# Schematic_Interface_Lio_with_IC.net
KiCad netlist of a schematic drawn in Altium Designer
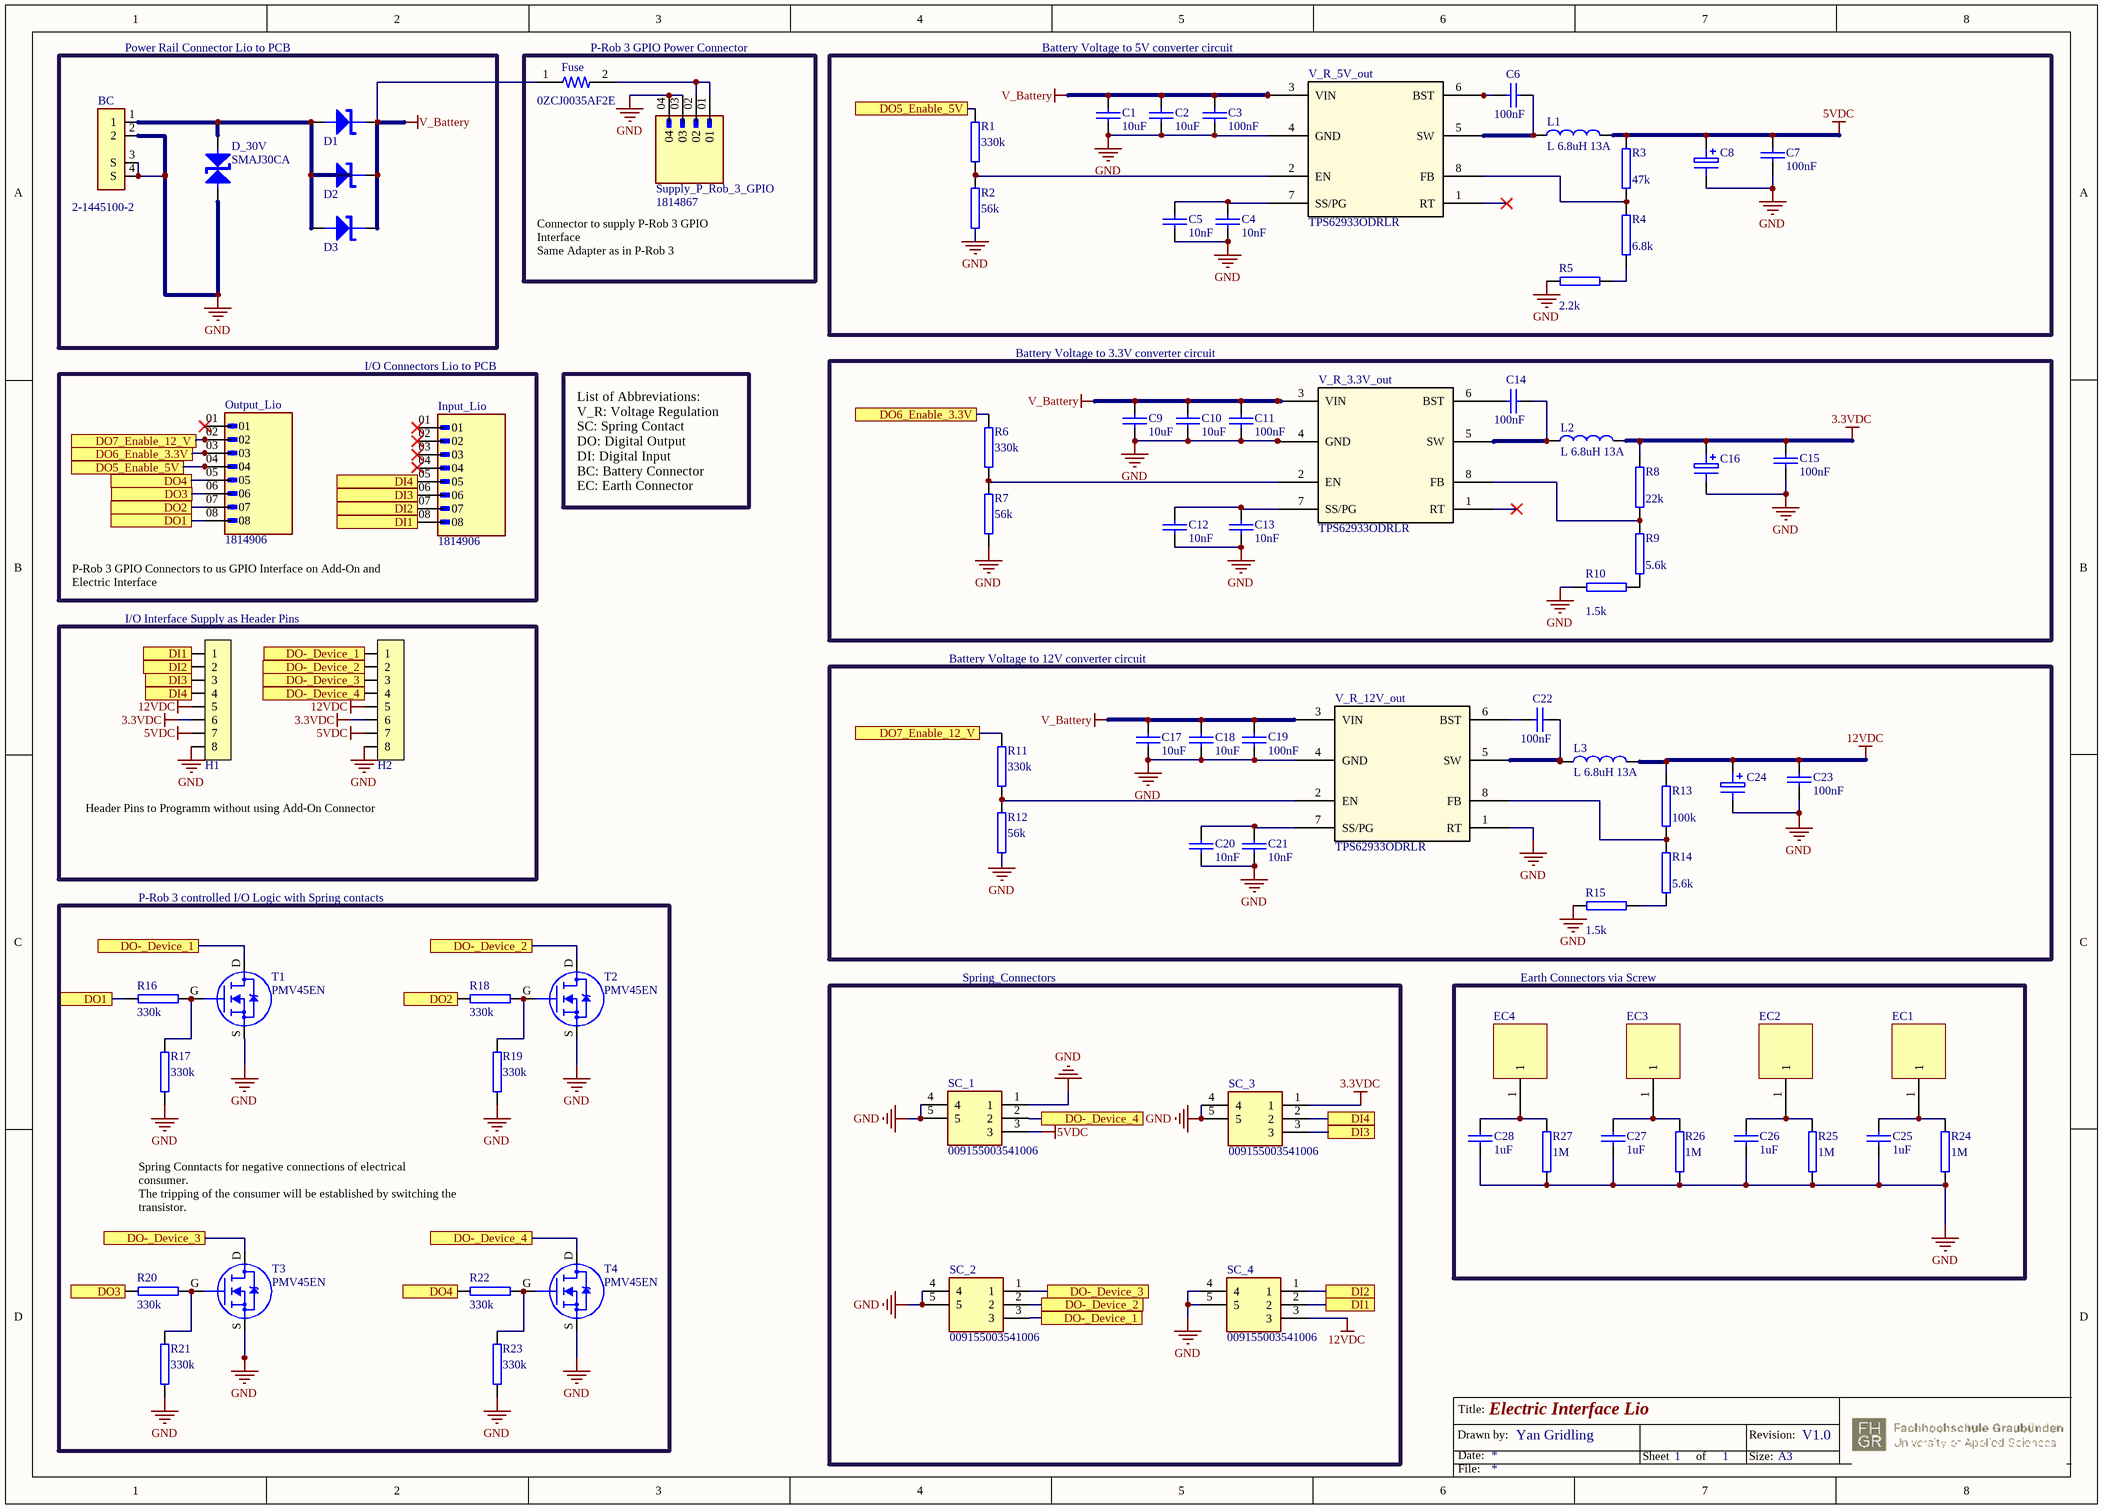
[diagram p0: Schematic_Interface_Lio_with_IC.SchDoc]

(export (version "E")
  (design (tool "Eeschema 10.0.6"))
  (components
    (comp (ref "BC")
      (value "2-1445100-2")
      (footprint "2-1445100-2")
      (description "Micro MATE-N-LOK 2 Position Surface Mount Single Row Straight 3 mm Pin Header")
      (fields (field (name "MF") "TE Connectivity") (field (name "MP") "2-1445053-2"))
      (libsource (lib "Electric_Interface_Lib") (part "2-1445100-2"))
    )
    (comp (ref "C1")
      (value "10uF")
      (footprint "C_1210_A")
      (fields
        (field (name "TOLERANCE") "10%")
        (field (name "VOLTAGE") "50V")
        (field (name "Comment") "C 10uF 1210")
      )
      (libsource (lib "FHGR_Altium_database") (part "Capacitor"))
    )
    (comp (ref "C2")
      (value "10uF")
      (footprint "C_1210_A")
      (fields
        (field (name "TOLERANCE") "10%")
        (field (name "VOLTAGE") "50V")
        (field (name "Comment") "C 10uF 1210")
      )
      (libsource (lib "FHGR_Altium_database") (part "Capacitor"))
    )
    (comp (ref "C3")
      (value "100nF")
      (footprint "0603")
      (fields
        (field (name "TOLERANCE") "-20%/+80%")
        (field (name "VOLTAGE") "50V")
        (field (name "Comment") "C 100nF 0603")
      )
      (libsource (lib "FHGR_Altium_database") (part "Capacitor"))
    )
    (comp (ref "C4")
      (value "10nF")
      (footprint "0603")
      (fields
        (field (name "TOLERANCE") "10%")
        (field (name "VOLTAGE") "50V")
        (field (name "Comment") "C 10nF 0603")
      )
      (libsource (lib "FHGR_Altium_database") (part "Capacitor"))
    )
    (comp (ref "C5")
      (value "10nF")
      (footprint "0603")
      (fields
        (field (name "TOLERANCE") "10%")
        (field (name "VOLTAGE") "50V")
        (field (name "Comment") "C 10nF 0603")
      )
      (libsource (lib "FHGR_Altium_database") (part "Capacitor"))
    )
    (comp (ref "C6")
      (value "100nF")
      (footprint "0603")
      (fields
        (field (name "TOLERANCE") "-20%/+80%")
        (field (name "VOLTAGE") "50V")
        (field (name "Comment") "C 100nF 0603")
      )
      (libsource (lib "FHGR_Altium_database") (part "Capacitor"))
    )
    (comp (ref "C7")
      (value "100nF")
      (footprint "0603")
      (fields
        (field (name "TOLERANCE") "-20%/+80%")
        (field (name "VOLTAGE") "50V")
        (field (name "Comment") "C 100nF 0603")
      )
      (libsource (lib "FHGR_Altium_database") (part "Capacitor"))
    )
    (comp (ref "C8")
      (value "C 47uF ALUM")
      (footprint "HA1C470WR")
      (fields (field (name "TOLERANCE") "20%") (field (name "VOLTAGE") "16V"))
      (libsource (lib "FHGR_Altium_database") (part "Capacitor_Pol"))
    )
    (comp (ref "C9")
      (value "10uF")
      (footprint "C_1210_A")
      (fields
        (field (name "TOLERANCE") "10%")
        (field (name "VOLTAGE") "50V")
        (field (name "Comment") "C 10uF 1210")
      )
      (libsource (lib "FHGR_Altium_database") (part "Capacitor"))
    )
    (comp (ref "C10")
      (value "10uF")
      (footprint "C_1210_A")
      (fields
        (field (name "TOLERANCE") "10%")
        (field (name "VOLTAGE") "50V")
        (field (name "Comment") "C 10uF 1210")
      )
      (libsource (lib "FHGR_Altium_database") (part "Capacitor"))
    )
    (comp (ref "C11")
      (value "100nF")
      (footprint "0603")
      (fields
        (field (name "TOLERANCE") "-20%/+80%")
        (field (name "VOLTAGE") "50V")
        (field (name "Comment") "C 100nF 0603")
      )
      (libsource (lib "FHGR_Altium_database") (part "Capacitor"))
    )
    (comp (ref "C12")
      (value "10nF")
      (footprint "0603")
      (fields
        (field (name "TOLERANCE") "10%")
        (field (name "VOLTAGE") "50V")
        (field (name "Comment") "C 10nF 0603")
      )
      (libsource (lib "FHGR_Altium_database") (part "Capacitor"))
    )
    (comp (ref "C13")
      (value "10nF")
      (footprint "0603")
      (fields
        (field (name "TOLERANCE") "10%")
        (field (name "VOLTAGE") "50V")
        (field (name "Comment") "C 10nF 0603")
      )
      (libsource (lib "FHGR_Altium_database") (part "Capacitor"))
    )
    (comp (ref "C14")
      (value "100nF")
      (footprint "0603")
      (fields
        (field (name "TOLERANCE") "-20%/+80%")
        (field (name "VOLTAGE") "50V")
        (field (name "Comment") "C 100nF 0603")
      )
      (libsource (lib "FHGR_Altium_database") (part "Capacitor"))
    )
    (comp (ref "C15")
      (value "100nF")
      (footprint "0603")
      (fields
        (field (name "TOLERANCE") "-20%/+80%")
        (field (name "VOLTAGE") "50V")
        (field (name "Comment") "C 100nF 0603")
      )
      (libsource (lib "FHGR_Altium_database") (part "Capacitor"))
    )
    (comp (ref "C16")
      (value "C 47uF ALUM")
      (footprint "HA1C470WR")
      (fields (field (name "TOLERANCE") "20%") (field (name "VOLTAGE") "16V"))
      (libsource (lib "FHGR_Altium_database") (part "Capacitor_Pol"))
    )
    (comp (ref "C17")
      (value "10uF")
      (footprint "C_1210_A")
      (fields
        (field (name "TOLERANCE") "10%")
        (field (name "VOLTAGE") "50V")
        (field (name "Comment") "C 10uF 1210")
      )
      (libsource (lib "FHGR_Altium_database") (part "Capacitor"))
    )
    (comp (ref "C18")
      (value "10uF")
      (footprint "C_1210_A")
      (fields
        (field (name "TOLERANCE") "10%")
        (field (name "VOLTAGE") "50V")
        (field (name "Comment") "C 10uF 1210")
      )
      (libsource (lib "FHGR_Altium_database") (part "Capacitor"))
    )
    (comp (ref "C19")
      (value "100nF")
      (footprint "0603")
      (fields
        (field (name "TOLERANCE") "-20%/+80%")
        (field (name "VOLTAGE") "50V")
        (field (name "Comment") "C 100nF 0603")
      )
      (libsource (lib "FHGR_Altium_database") (part "Capacitor"))
    )
    (comp (ref "C20")
      (value "10nF")
      (footprint "0603")
      (fields
        (field (name "TOLERANCE") "10%")
        (field (name "VOLTAGE") "50V")
        (field (name "Comment") "C 10nF 0603")
      )
      (libsource (lib "FHGR_Altium_database") (part "Capacitor"))
    )
    (comp (ref "C21")
      (value "10nF")
      (footprint "0603")
      (fields
        (field (name "TOLERANCE") "10%")
        (field (name "VOLTAGE") "50V")
        (field (name "Comment") "C 10nF 0603")
      )
      (libsource (lib "FHGR_Altium_database") (part "Capacitor"))
    )
    (comp (ref "C22")
      (value "100nF")
      (footprint "0603")
      (fields
        (field (name "TOLERANCE") "-20%/+80%")
        (field (name "VOLTAGE") "50V")
        (field (name "Comment") "C 100nF 0603")
      )
      (libsource (lib "FHGR_Altium_database") (part "Capacitor"))
    )
    (comp (ref "C23")
      (value "100nF")
      (footprint "0603")
      (fields
        (field (name "TOLERANCE") "-20%/+80%")
        (field (name "VOLTAGE") "50V")
        (field (name "Comment") "C 100nF 0603")
      )
      (libsource (lib "FHGR_Altium_database") (part "Capacitor"))
    )
    (comp (ref "C24")
      (value "C 47uF ALUM")
      (footprint "HA1C470WR")
      (fields (field (name "TOLERANCE") "20%") (field (name "VOLTAGE") "16V"))
      (libsource (lib "FHGR_Altium_database") (part "Capacitor_Pol"))
    )
    (comp (ref "C25")
      (value "1uF")
      (footprint "0603")
      (fields
        (field (name "TOLERANCE") "10%")
        (field (name "VOLTAGE") "25V")
        (field (name "Comment") "C 1uF 0603")
      )
      (libsource (lib "FHGR_Altium_database") (part "Capacitor"))
    )
    (comp (ref "C26")
      (value "1uF")
      (footprint "0603")
      (fields
        (field (name "TOLERANCE") "10%")
        (field (name "VOLTAGE") "25V")
        (field (name "Comment") "C 1uF 0603")
      )
      (libsource (lib "FHGR_Altium_database") (part "Capacitor"))
    )
    (comp (ref "C27")
      (value "1uF")
      (footprint "0603")
      (fields
        (field (name "TOLERANCE") "10%")
        (field (name "VOLTAGE") "25V")
        (field (name "Comment") "C 1uF 0603")
      )
      (libsource (lib "FHGR_Altium_database") (part "Capacitor"))
    )
    (comp (ref "C28")
      (value "1uF")
      (footprint "0603")
      (fields
        (field (name "TOLERANCE") "10%")
        (field (name "VOLTAGE") "25V")
        (field (name "Comment") "C 1uF 0603")
      )
      (libsource (lib "FHGR_Altium_database") (part "Capacitor"))
    )
    (comp (ref "D1")
      (value "Schottky 60V/2A")
      (footprint "SOD-123FL")
      (fields (field (name "VOLTAGE") "60V"))
      (libsource (lib "FHGR_Altium_database") (part "SchottkyDiode"))
    )
    (comp (ref "D2")
      (value "Schottky 60V/2A")
      (footprint "SOD-123FL")
      (fields (field (name "VOLTAGE") "60V"))
      (libsource (lib "FHGR_Altium_database") (part "SchottkyDiode"))
    )
    (comp (ref "D3")
      (value "Schottky 60V/2A")
      (footprint "SOD-123FL")
      (fields (field (name "VOLTAGE") "60V"))
      (libsource (lib "FHGR_Altium_database") (part "SchottkyDiode"))
    )
    (comp (ref "D_30V")
      (value "SMAJ30CA")
      (footprint "SMA")
      (description "Cera Diode 30 Volt Overvoltage protection.")
      (fields (field (name "VOLTAGE") "30V"))
      (libsource (lib "FHGR_Altium_database") (part "CeraDiode"))
    )
    (comp (ref "EC1")
      (value "Screw_Earth_Connection")
      (footprint "Screw_Earth_Connector_Pad")
      (libsource (lib "Electric_Interface_Lib") (part "Screw_Earth_Connection"))
    )
    (comp (ref "EC2")
      (value "Screw_Earth_Connection")
      (footprint "Screw_Earth_Connector_Pad")
      (libsource (lib "Electric_Interface_Lib") (part "Screw_Earth_Connection"))
    )
    (comp (ref "EC3")
      (value "Screw_Earth_Connection")
      (footprint "Screw_Earth_Connector_Pad")
      (libsource (lib "Electric_Interface_Lib") (part "Screw_Earth_Connection"))
    )
    (comp (ref "EC4")
      (value "Screw_Earth_Connection")
      (footprint "Screw_Earth_Connector_Pad")
      (libsource (lib "Electric_Interface_Lib") (part "Screw_Earth_Connection"))
    )
    (comp (ref "Fuse")
      (value "0ZCJ0035AF2E")
      (footprint "RESC3216X125N")
      (description "1206 SMT PPTC ¦ 0.35 Ih ¦ 30V")
      (fields (field (name "MF") "Bel Fuse"))
      (libsource (lib "Electric_Interface_Lib") (part "0ZCJ0035AF2E"))
    )
    (comp (ref "H1")
      (value "8Pin_Male")
      (footprint "Header1x8_254")
      (libsource (lib "FHGR_Altium_database") (part "Connector8Pin"))
    )
    (comp (ref "H2")
      (value "8Pin_Male")
      (footprint "Header1x8_254")
      (libsource (lib "FHGR_Altium_database") (part "Connector8Pin"))
    )
    (comp (ref "Input_Lio")
      (value "1814906")
      (footprint "PHOENIX_1814906")
      (fields (field (name "MF") "{'manufacturer': u'Phoenix Contact'}"))
      (libsource (lib "Electric_Interface_Lib") (part "1814906"))
    )
    (comp (ref "L1")
      (value "L 6.8uH 13A")
      (footprint "SRP1040VA-6R8M")
      (libsource (lib "Electric_Interface_Lib") (part "SRP1040VA-6R8M"))
    )
    (comp (ref "L2")
      (value "L 6.8uH 13A")
      (footprint "SRP1040VA-6R8M")
      (libsource (lib "Electric_Interface_Lib") (part "SRP1040VA-6R8M"))
    )
    (comp (ref "L3")
      (value "L 6.8uH 13A")
      (footprint "SRP1040VA-6R8M")
      (libsource (lib "Electric_Interface_Lib") (part "SRP1040VA-6R8M"))
    )
    (comp (ref "Output_Lio")
      (value "1814906")
      (footprint "PHOENIX_1814906")
      (fields (field (name "MF") "{'manufacturer': u'Phoenix Contact'}"))
      (libsource (lib "Electric_Interface_Lib") (part "1814906"))
    )
    (comp (ref "R1")
      (value "330k")
      (footprint "0805")
      (fields (field (name "TOLERANCE") "1%") (field (name "Comment") "R 330K 0805"))
      (libsource (lib "FHGR_Altium_database") (part "Resistor"))
    )
    (comp (ref "R2")
      (value "56k")
      (footprint "0805")
      (fields (field (name "TOLERANCE") "1%") (field (name "Comment") "R 56K 0805"))
      (libsource (lib "FHGR_Altium_database") (part "Resistor"))
    )
    (comp (ref "R3")
      (value "47k")
      (footprint "0805")
      (fields (field (name "TOLERANCE") "1%") (field (name "Comment") "R 47K 0805"))
      (libsource (lib "FHGR_Altium_database") (part "Resistor"))
    )
    (comp (ref "R4")
      (value "6.8k")
      (footprint "0805")
      (fields (field (name "TOLERANCE") "1%") (field (name "Comment") "R 6K8 0805"))
      (libsource (lib "FHGR_Altium_database") (part "Resistor"))
    )
    (comp (ref "R5")
      (value "2.2k")
      (footprint "0805")
      (fields (field (name "TOLERANCE") "1%") (field (name "Comment") "R 2K2 0805"))
      (libsource (lib "FHGR_Altium_database") (part "Resistor"))
    )
    (comp (ref "R6")
      (value "330k")
      (footprint "0805")
      (fields (field (name "TOLERANCE") "1%") (field (name "Comment") "R 330K 0805"))
      (libsource (lib "FHGR_Altium_database") (part "Resistor"))
    )
    (comp (ref "R7")
      (value "56k")
      (footprint "0805")
      (fields (field (name "TOLERANCE") "1%") (field (name "Comment") "R 56K 0805"))
      (libsource (lib "FHGR_Altium_database") (part "Resistor"))
    )
    (comp (ref "R8")
      (value "22k")
      (footprint "0805")
      (fields (field (name "TOLERANCE") "1%") (field (name "Comment") "R 22K 0805"))
      (libsource (lib "FHGR_Altium_database") (part "Resistor"))
    )
    (comp (ref "R9")
      (value "5.6k")
      (footprint "0805")
      (fields (field (name "TOLERANCE") "1%") (field (name "Comment") "R 5K6 0805"))
      (libsource (lib "FHGR_Altium_database") (part "Resistor"))
    )
    (comp (ref "R10")
      (value "1.5k")
      (footprint "0805")
      (fields (field (name "TOLERANCE") "1%") (field (name "Comment") "R 1K5 0805"))
      (libsource (lib "FHGR_Altium_database") (part "Resistor"))
    )
    (comp (ref "R11")
      (value "330k")
      (footprint "0805")
      (fields (field (name "TOLERANCE") "1%") (field (name "Comment") "R 330K 0805"))
      (libsource (lib "FHGR_Altium_database") (part "Resistor"))
    )
    (comp (ref "R12")
      (value "56k")
      (footprint "0805")
      (fields (field (name "TOLERANCE") "1%") (field (name "Comment") "R 56K 0805"))
      (libsource (lib "FHGR_Altium_database") (part "Resistor"))
    )
    (comp (ref "R13")
      (value "100k")
      (footprint "0805")
      (fields (field (name "TOLERANCE") "1%") (field (name "Comment") "R 100K 0805"))
      (libsource (lib "FHGR_Altium_database") (part "Resistor"))
    )
    (comp (ref "R14")
      (value "5.6k")
      (footprint "0805")
      (fields (field (name "TOLERANCE") "1%") (field (name "Comment") "R 5K6 0805"))
      (libsource (lib "FHGR_Altium_database") (part "Resistor"))
    )
    (comp (ref "R15")
      (value "1.5k")
      (footprint "0805")
      (fields (field (name "TOLERANCE") "1%") (field (name "Comment") "R 1K5 0805"))
      (libsource (lib "FHGR_Altium_database") (part "Resistor"))
    )
    (comp (ref "R16")
      (value "330k")
      (footprint "0805")
      (fields (field (name "TOLERANCE") "1%") (field (name "Comment") "R 330K 0805"))
      (libsource (lib "FHGR_Altium_database") (part "Resistor"))
    )
    (comp (ref "R17")
      (value "330k")
      (footprint "0805")
      (fields (field (name "TOLERANCE") "1%") (field (name "Comment") "R 330K 0805"))
      (libsource (lib "FHGR_Altium_database") (part "Resistor"))
    )
    (comp (ref "R18")
      (value "330k")
      (footprint "0805")
      (fields (field (name "TOLERANCE") "1%") (field (name "Comment") "R 330K 0805"))
      (libsource (lib "FHGR_Altium_database") (part "Resistor"))
    )
    (comp (ref "R19")
      (value "330k")
      (footprint "0805")
      (fields (field (name "TOLERANCE") "1%") (field (name "Comment") "R 330K 0805"))
      (libsource (lib "FHGR_Altium_database") (part "Resistor"))
    )
    (comp (ref "R20")
      (value "330k")
      (footprint "0805")
      (fields (field (name "TOLERANCE") "1%") (field (name "Comment") "R 330K 0805"))
      (libsource (lib "FHGR_Altium_database") (part "Resistor"))
    )
    (comp (ref "R21")
      (value "330k")
      (footprint "0805")
      (fields (field (name "TOLERANCE") "1%") (field (name "Comment") "R 330K 0805"))
      (libsource (lib "FHGR_Altium_database") (part "Resistor"))
    )
    (comp (ref "R22")
      (value "330k")
      (footprint "0805")
      (fields (field (name "TOLERANCE") "1%") (field (name "Comment") "R 330K 0805"))
      (libsource (lib "FHGR_Altium_database") (part "Resistor"))
    )
    (comp (ref "R23")
      (value "330k")
      (footprint "0805")
      (fields (field (name "TOLERANCE") "1%") (field (name "Comment") "R 330K 0805"))
      (libsource (lib "FHGR_Altium_database") (part "Resistor"))
    )
    (comp (ref "R24")
      (value "1M")
      (footprint "0805")
      (fields (field (name "TOLERANCE") "1%") (field (name "Comment") "R 1M 0805"))
      (libsource (lib "FHGR_Altium_database") (part "Resistor"))
    )
    (comp (ref "R25")
      (value "1M")
      (footprint "0805")
      (fields (field (name "TOLERANCE") "1%") (field (name "Comment") "R 1M 0805"))
      (libsource (lib "FHGR_Altium_database") (part "Resistor"))
    )
    (comp (ref "R26")
      (value "1M")
      (footprint "0805")
      (fields (field (name "TOLERANCE") "1%") (field (name "Comment") "R 1M 0805"))
      (libsource (lib "FHGR_Altium_database") (part "Resistor"))
    )
    (comp (ref "R27")
      (value "1M")
      (footprint "0805")
      (fields (field (name "TOLERANCE") "1%") (field (name "Comment") "R 1M 0805"))
      (libsource (lib "FHGR_Altium_database") (part "Resistor"))
    )
    (comp (ref "SC_1")
      (value "009155003541006")
      (footprint "009155003541006")
      (description "Connector")
      (fields (field (name "MOUSER PART NUMBER") "581-009155003541006"))
      (libsource (lib "Electric_Interface_Lib") (part "009155003541006"))
    )
    (comp (ref "SC_2")
      (value "009155003541006")
      (footprint "009155003541006")
      (description "Connector")
      (fields (field (name "MOUSER PART NUMBER") "581-009155003541006"))
      (libsource (lib "Electric_Interface_Lib") (part "009155003541006"))
    )
    (comp (ref "SC_3")
      (value "009155003541006")
      (footprint "009155003541006")
      (description "Connector")
      (fields (field (name "MOUSER PART NUMBER") "581-009155003541006"))
      (libsource (lib "Electric_Interface_Lib") (part "009155003541006"))
    )
    (comp (ref "SC_4")
      (value "009155003541006")
      (footprint "009155003541006")
      (description "Connector")
      (fields (field (name "MOUSER PART NUMBER") "581-009155003541006"))
      (libsource (lib "Electric_Interface_Lib") (part "009155003541006"))
    )
    (comp (ref "Supply_P_Rob_3_GPIO")
      (value "1814867")
      (footprint "PHOENIX_1814867")
      (description "Pluggable Header 2.5mm 20AWG 160V 6A 4 Position COMBICON PTSM Series ¦ Phoenix Contact 1814867")
      (fields (field (name "MF") "Phoenix Contact"))
      (libsource (lib "Electric_Interface_Lib") (part "1814867"))
    )
    (comp (ref "T1")
      (value "PMV45EN")
      (footprint "SOT-23-FET")
      (fields (field (name "VOLTAGE") "30V"))
      (libsource (lib "FHGR_Altium_database") (part "NMOSEnhancement_DIODE"))
    )
    (comp (ref "T2")
      (value "PMV45EN")
      (footprint "SOT-23-FET")
      (fields (field (name "VOLTAGE") "30V"))
      (libsource (lib "FHGR_Altium_database") (part "NMOSEnhancement_DIODE"))
    )
    (comp (ref "T3")
      (value "PMV45EN")
      (footprint "SOT-23-FET")
      (fields (field (name "VOLTAGE") "30V"))
      (libsource (lib "FHGR_Altium_database") (part "NMOSEnhancement_DIODE"))
    )
    (comp (ref "T4")
      (value "PMV45EN")
      (footprint "SOT-23-FET")
      (fields (field (name "VOLTAGE") "30V"))
      (libsource (lib "FHGR_Altium_database") (part "NMOSEnhancement_DIODE"))
    )
    (comp (ref "V_R_3.3V_out")
      (value "TPS62933ODRLR")
      (footprint "SOT5X3-8_DRL_TEX")
      (description "Buck Converter")
      (libsource (lib "Electric_Interface_Lib") (part "TPS62933ODRLR"))
    )
    (comp (ref "V_R_5V_out")
      (value "TPS62933ODRLR")
      (footprint "SOT5X3-8_DRL_TEX")
      (description "Buck Converter")
      (libsource (lib "Electric_Interface_Lib") (part "TPS62933ODRLR"))
    )
    (comp (ref "V_R_12V_out")
      (value "TPS62933ODRLR")
      (footprint "SOT5X3-8_DRL_TEX")
      (description "Buck Converter")
      (libsource (lib "Electric_Interface_Lib") (part "TPS62933ODRLR"))
    )
  )
  (nets
    (net (code "1") (name "/DI1") (class "Default")
      (node (ref "H1") (pin "1") (pinfunction "1_1") (pintype "passive"))
      (node (ref "Input_Lio") (pin "08") (pinfunction "08_08") (pintype "passive"))
      (node (ref "SC_4") (pin "2") (pinfunction "2_2") (pintype "passive"))
    )
    (net (code "2") (name "/DI2") (class "Default")
      (node (ref "H1") (pin "2") (pinfunction "2_2") (pintype "passive"))
      (node (ref "Input_Lio") (pin "07") (pinfunction "07_07") (pintype "passive"))
      (node (ref "SC_4") (pin "1") (pinfunction "1_1") (pintype "passive"))
    )
    (net (code "3") (name "/DI3") (class "Default")
      (node (ref "H1") (pin "3") (pinfunction "3_3") (pintype "passive"))
      (node (ref "Input_Lio") (pin "06") (pinfunction "06_06") (pintype "passive"))
      (node (ref "SC_3") (pin "3") (pinfunction "3_3") (pintype "passive"))
    )
    (net (code "4") (name "/DI4") (class "Default")
      (node (ref "H1") (pin "4") (pinfunction "4_4") (pintype "passive"))
      (node (ref "Input_Lio") (pin "05") (pinfunction "05_05") (pintype "passive"))
      (node (ref "SC_3") (pin "2") (pinfunction "2_2") (pintype "passive"))
    )
    (net (code "5") (name "/DO-_Device_1") (class "Default")
      (node (ref "H2") (pin "1") (pinfunction "1_1") (pintype "passive"))
      (node (ref "SC_2") (pin "3") (pinfunction "3_3") (pintype "passive"))
      (node (ref "T1") (pin "D") (pintype "passive"))
    )
    (net (code "6") (name "/DO-_Device_2") (class "Default")
      (node (ref "H2") (pin "2") (pinfunction "2_2") (pintype "passive"))
      (node (ref "SC_2") (pin "2") (pinfunction "2_2") (pintype "passive"))
      (node (ref "T2") (pin "D") (pintype "passive"))
    )
    (net (code "7") (name "/DO-_Device_3") (class "Default")
      (node (ref "H2") (pin "3") (pinfunction "3_3") (pintype "passive"))
      (node (ref "SC_2") (pin "1") (pinfunction "1_1") (pintype "passive"))
      (node (ref "T3") (pin "D") (pintype "passive"))
    )
    (net (code "8") (name "/DO-_Device_4") (class "Default")
      (node (ref "H2") (pin "4") (pinfunction "4_4") (pintype "passive"))
      (node (ref "SC_1") (pin "2") (pinfunction "2_2") (pintype "passive"))
      (node (ref "T4") (pin "D") (pintype "passive"))
    )
    (net (code "9") (name "/DO1") (class "Default")
      (node (ref "Output_Lio") (pin "08") (pinfunction "08_08") (pintype "passive"))
      (node (ref "R16") (pin "1") (pintype "passive"))
    )
    (net (code "10") (name "/DO2") (class "Default")
      (node (ref "Output_Lio") (pin "07") (pinfunction "07_07") (pintype "passive"))
      (node (ref "R18") (pin "2") (pintype "passive"))
    )
    (net (code "11") (name "/DO3") (class "Default")
      (node (ref "Output_Lio") (pin "06") (pinfunction "06_06") (pintype "passive"))
      (node (ref "R20") (pin "1") (pintype "passive"))
    )
    (net (code "12") (name "/DO4") (class "Default")
      (node (ref "Output_Lio") (pin "05") (pinfunction "05_05") (pintype "passive"))
      (node (ref "R22") (pin "2") (pintype "passive"))
    )
    (net (code "13") (name "/DO5_Enable_5V") (class "Default")
      (node (ref "Output_Lio") (pin "04") (pinfunction "04_04") (pintype "passive"))
      (node (ref "R1") (pin "1") (pintype "passive"))
    )
    (net (code "14") (name "/DO6_Enable_3.3V") (class "Default")
      (node (ref "Output_Lio") (pin "03") (pinfunction "03_03") (pintype "passive"))
      (node (ref "R6") (pin "1") (pintype "passive"))
    )
    (net (code "15") (name "/DO7_Enable_12_V") (class "Default")
      (node (ref "Output_Lio") (pin "02") (pinfunction "02_02") (pintype "passive"))
      (node (ref "R11") (pin "1") (pintype "passive"))
    )
    (net (code "16") (name "3.3VDC") (class "Default")
      (node (ref "C15") (pin "1") (pintype "passive"))
      (node (ref "C16") (pin "1") (pintype "passive"))
      (node (ref "H1") (pin "6") (pinfunction "6_6") (pintype "passive"))
      (node (ref "H2") (pin "6") (pinfunction "6_6") (pintype "passive"))
      (node (ref "L2") (pin "2") (pintype "passive"))
      (node (ref "R8") (pin "2") (pintype "passive"))
      (node (ref "SC_3") (pin "1") (pinfunction "1_1") (pintype "passive"))
    )
    (net (code "17") (name "5VDC") (class "Default")
      (node (ref "C7") (pin "1") (pintype "passive"))
      (node (ref "C8") (pin "1") (pintype "passive"))
      (node (ref "H1") (pin "7") (pinfunction "7_7") (pintype "passive"))
      (node (ref "H2") (pin "7") (pinfunction "7_7") (pintype "passive"))
      (node (ref "L1") (pin "2") (pintype "passive"))
      (node (ref "R3") (pin "2") (pintype "passive"))
      (node (ref "SC_1") (pin "3") (pinfunction "3_3") (pintype "passive"))
    )
    (net (code "18") (name "12VDC") (class "Default")
      (node (ref "C23") (pin "1") (pintype "passive"))
      (node (ref "C24") (pin "1") (pintype "passive"))
      (node (ref "H1") (pin "5") (pinfunction "5_5") (pintype "passive"))
      (node (ref "H2") (pin "5") (pinfunction "5_5") (pintype "passive"))
      (node (ref "L3") (pin "2") (pintype "passive"))
      (node (ref "R13") (pin "2") (pintype "passive"))
      (node (ref "SC_4") (pin "3") (pinfunction "3_3") (pintype "passive"))
    )
    (net (code "19") (name "GND") (class "Default")
      (node (ref "BC") (pin "2") (pinfunction "2_2") (pintype "passive"))
      (node (ref "BC") (pin "3") (pinfunction "S_3") (pintype "passive"))
      (node (ref "BC") (pin "4") (pinfunction "S_4") (pintype "passive"))
      (node (ref "C1") (pin "2") (pintype "passive"))
      (node (ref "C10") (pin "2") (pintype "passive"))
      (node (ref "C11") (pin "2") (pintype "passive"))
      (node (ref "C12") (pin "2") (pintype "passive"))
      (node (ref "C13") (pin "2") (pintype "passive"))
      (node (ref "C15") (pin "2") (pintype "passive"))
      (node (ref "C16") (pin "2") (pintype "passive"))
      (node (ref "C17") (pin "2") (pintype "passive"))
      (node (ref "C18") (pin "2") (pintype "passive"))
      (node (ref "C19") (pin "2") (pintype "passive"))
      (node (ref "C2") (pin "2") (pintype "passive"))
      (node (ref "C20") (pin "2") (pintype "passive"))
      (node (ref "C21") (pin "2") (pintype "passive"))
      (node (ref "C23") (pin "2") (pintype "passive"))
      (node (ref "C24") (pin "2") (pintype "passive"))
      (node (ref "C25") (pin "2") (pintype "passive"))
      (node (ref "C26") (pin "1") (pintype "passive"))
      (node (ref "C27") (pin "1") (pintype "passive"))
      (node (ref "C28") (pin "1") (pintype "passive"))
      (node (ref "C3") (pin "2") (pintype "passive"))
      (node (ref "C4") (pin "2") (pintype "passive"))
      (node (ref "C5") (pin "2") (pintype "passive"))
      (node (ref "C7") (pin "2") (pintype "passive"))
      (node (ref "C8") (pin "2") (pintype "passive"))
      (node (ref "C9") (pin "2") (pintype "passive"))
      (node (ref "D_30V") (pin "K") (pintype "passive"))
      (node (ref "H1") (pin "8") (pinfunction "8_8") (pintype "passive"))
      (node (ref "H2") (pin "8") (pinfunction "8_8") (pintype "passive"))
      (node (ref "R10") (pin "1") (pintype "passive"))
      (node (ref "R12") (pin "2") (pintype "passive"))
      (node (ref "R15") (pin "1") (pintype "passive"))
      (node (ref "R17") (pin "1") (pintype "passive"))
      (node (ref "R19") (pin "2") (pintype "passive"))
      (node (ref "R2") (pin "2") (pintype "passive"))
      (node (ref "R21") (pin "1") (pintype "passive"))
      (node (ref "R23") (pin "2") (pintype "passive"))
      (node (ref "R24") (pin "2") (pintype "passive"))
      (node (ref "R25") (pin "2") (pintype "passive"))
      (node (ref "R26") (pin "2") (pintype "passive"))
      (node (ref "R27") (pin "2") (pintype "passive"))
      (node (ref "R5") (pin "1") (pintype "passive"))
      (node (ref "R7") (pin "2") (pintype "passive"))
      (node (ref "SC_1") (pin "1") (pinfunction "1_1") (pintype "passive"))
      (node (ref "SC_1") (pin "4") (pinfunction "4_4") (pintype "passive"))
      (node (ref "SC_1") (pin "5") (pinfunction "5_5") (pintype "passive"))
      (node (ref "SC_2") (pin "4") (pinfunction "4_4") (pintype "passive"))
      (node (ref "SC_2") (pin "5") (pinfunction "5_5") (pintype "passive"))
      (node (ref "SC_3") (pin "4") (pinfunction "4_4") (pintype "passive"))
      (node (ref "SC_3") (pin "5") (pinfunction "5_5") (pintype "passive"))
      (node (ref "SC_4") (pin "4") (pinfunction "4_4") (pintype "passive"))
      (node (ref "SC_4") (pin "5") (pinfunction "5_5") (pintype "passive"))
      (node (ref "Supply_P_Rob_3_GPIO") (pin "03") (pinfunction "03_03") (pintype "passive"))
      (node (ref "Supply_P_Rob_3_GPIO") (pin "04") (pinfunction "04_04") (pintype "passive"))
      (node (ref "T1") (pin "S") (pintype "passive"))
      (node (ref "T2") (pin "S") (pintype "passive"))
      (node (ref "T3") (pin "S") (pintype "passive"))
      (node (ref "T4") (pin "S") (pintype "passive"))
      (node (ref "V_R_12V_out") (pin "1") (pinfunction "RT_1") (pintype "passive"))
      (node (ref "V_R_12V_out") (pin "4") (pinfunction "GND_4") (pintype "power_in"))
      (node (ref "V_R_3.3V_out") (pin "4") (pinfunction "GND_4") (pintype "power_in"))
      (node (ref "V_R_5V_out") (pin "4") (pinfunction "GND_4") (pintype "power_in"))
    )
    (net (code "20") (name "Net-(BC-Pad1)") (class "Default")
      (node (ref "BC") (pin "1") (pinfunction "1_1") (pintype "passive"))
      (node (ref "D1") (pin "A") (pintype "passive"))
      (node (ref "D2") (pin "A") (pintype "passive"))
      (node (ref "D3") (pin "A") (pintype "passive"))
      (node (ref "D_30V") (pin "A") (pintype "passive"))
    )
    (net (code "21") (name "Net-(C25-Pad1)") (class "Default")
      (node (ref "C25") (pin "1") (pintype "passive"))
      (node (ref "EC1") (pin "1") (pinfunction "1_1") (pintype "passive"))
      (node (ref "R24") (pin "1") (pintype "passive"))
    )
    (net (code "22") (name "Net-(C26-Pad2)") (class "Default")
      (node (ref "C26") (pin "2") (pintype "passive"))
      (node (ref "EC2") (pin "1") (pinfunction "1_1") (pintype "passive"))
      (node (ref "R25") (pin "1") (pintype "passive"))
    )
    (net (code "23") (name "Net-(C27-Pad2)") (class "Default")
      (node (ref "C27") (pin "2") (pintype "passive"))
      (node (ref "EC3") (pin "1") (pinfunction "1_1") (pintype "passive"))
      (node (ref "R26") (pin "1") (pintype "passive"))
    )
    (net (code "24") (name "Net-(C28-Pad2)") (class "Default")
      (node (ref "C28") (pin "2") (pintype "passive"))
      (node (ref "EC4") (pin "1") (pinfunction "1_1") (pintype "passive"))
      (node (ref "R27") (pin "1") (pintype "passive"))
    )
    (net (code "25") (name "Net-(Fuse-Pad2)") (class "Default")
      (node (ref "Fuse") (pin "2") (pinfunction "2_2") (pintype "passive"))
      (node (ref "Supply_P_Rob_3_GPIO") (pin "01") (pinfunction "01_01") (pintype "passive"))
      (node (ref "Supply_P_Rob_3_GPIO") (pin "02") (pinfunction "02_02") (pintype "passive"))
    )
    (net (code "26") (name "Net-(R4-Pad1)") (class "Default")
      (node (ref "R4") (pin "1") (pintype "passive"))
      (node (ref "R5") (pin "2") (pintype "passive"))
    )
    (net (code "27") (name "Net-(R10-Pad2)") (class "Default")
      (node (ref "R10") (pin "2") (pintype "passive"))
      (node (ref "R9") (pin "1") (pintype "passive"))
    )
    (net (code "28") (name "Net-(R14-Pad1)") (class "Default")
      (node (ref "R14") (pin "1") (pintype "passive"))
      (node (ref "R15") (pin "2") (pintype "passive"))
    )
    (net (code "29") (name "Net-(R16-Pad2)") (class "Default")
      (node (ref "R16") (pin "2") (pintype "passive"))
      (node (ref "R17") (pin "2") (pintype "passive"))
      (node (ref "T1") (pin "G") (pintype "passive"))
    )
    (net (code "30") (name "Net-(R18-Pad1)") (class "Default")
      (node (ref "R18") (pin "1") (pintype "passive"))
      (node (ref "R19") (pin "1") (pintype "passive"))
      (node (ref "T2") (pin "G") (pintype "passive"))
    )
    (net (code "31") (name "Net-(R20-Pad2)") (class "Default")
      (node (ref "R20") (pin "2") (pintype "passive"))
      (node (ref "R21") (pin "2") (pintype "passive"))
      (node (ref "T3") (pin "G") (pintype "passive"))
    )
    (net (code "32") (name "Net-(R22-Pad1)") (class "Default")
      (node (ref "R22") (pin "1") (pintype "passive"))
      (node (ref "R23") (pin "1") (pintype "passive"))
      (node (ref "T4") (pin "G") (pintype "passive"))
    )
    (net (code "33") (name "Net-(V_R_3.3V_out-BST)") (class "Default")
      (node (ref "C14") (pin "1") (pintype "passive"))
      (node (ref "V_R_3.3V_out") (pin "6") (pinfunction "BST_6") (pintype "power_in"))
    )
    (net (code "34") (name "Net-(V_R_3.3V_out-EN)") (class "Default")
      (node (ref "R6") (pin "2") (pintype "passive"))
      (node (ref "R7") (pin "1") (pintype "passive"))
      (node (ref "V_R_3.3V_out") (pin "2") (pinfunction "EN_2") (pintype "passive"))
    )
    (net (code "35") (name "Net-(V_R_3.3V_out-FB)") (class "Default")
      (node (ref "R8") (pin "1") (pintype "passive"))
      (node (ref "R9") (pin "2") (pintype "passive"))
      (node (ref "V_R_3.3V_out") (pin "8") (pinfunction "FB_8") (pintype "passive"))
    )
    (net (code "36") (name "Net-(V_R_3.3V_out-SS{slash}PG)") (class "Default")
      (node (ref "C12") (pin "1") (pintype "passive"))
      (node (ref "C13") (pin "1") (pintype "passive"))
      (node (ref "V_R_3.3V_out") (pin "7") (pinfunction "SS/PG_7") (pintype "passive"))
    )
    (net (code "37") (name "Net-(V_R_3.3V_out-SW)") (class "Default")
      (node (ref "C14") (pin "2") (pintype "passive"))
      (node (ref "L2") (pin "1") (pintype "passive"))
      (node (ref "V_R_3.3V_out") (pin "5") (pinfunction "SW_5") (pintype "power_in"))
    )
    (net (code "38") (name "Net-(V_R_5V_out-BST)") (class "Default")
      (node (ref "C6") (pin "1") (pintype "passive"))
      (node (ref "V_R_5V_out") (pin "6") (pinfunction "BST_6") (pintype "power_in"))
    )
    (net (code "39") (name "Net-(V_R_5V_out-EN)") (class "Default")
      (node (ref "R1") (pin "2") (pintype "passive"))
      (node (ref "R2") (pin "1") (pintype "passive"))
      (node (ref "V_R_5V_out") (pin "2") (pinfunction "EN_2") (pintype "passive"))
    )
    (net (code "40") (name "Net-(V_R_5V_out-FB)") (class "Default")
      (node (ref "R3") (pin "1") (pintype "passive"))
      (node (ref "R4") (pin "2") (pintype "passive"))
      (node (ref "V_R_5V_out") (pin "8") (pinfunction "FB_8") (pintype "passive"))
    )
    (net (code "41") (name "Net-(V_R_5V_out-SS{slash}PG)") (class "Default")
      (node (ref "C4") (pin "1") (pintype "passive"))
      (node (ref "C5") (pin "1") (pintype "passive"))
      (node (ref "V_R_5V_out") (pin "7") (pinfunction "SS/PG_7") (pintype "passive"))
    )
    (net (code "42") (name "Net-(V_R_5V_out-SW)") (class "Default")
      (node (ref "C6") (pin "2") (pintype "passive"))
      (node (ref "L1") (pin "1") (pintype "passive"))
      (node (ref "V_R_5V_out") (pin "5") (pinfunction "SW_5") (pintype "power_in"))
    )
    (net (code "43") (name "Net-(V_R_12V_out-BST)") (class "Default")
      (node (ref "C22") (pin "1") (pintype "passive"))
      (node (ref "V_R_12V_out") (pin "6") (pinfunction "BST_6") (pintype "power_in"))
    )
    (net (code "44") (name "Net-(V_R_12V_out-EN)") (class "Default")
      (node (ref "R11") (pin "2") (pintype "passive"))
      (node (ref "R12") (pin "1") (pintype "passive"))
      (node (ref "V_R_12V_out") (pin "2") (pinfunction "EN_2") (pintype "passive"))
    )
    (net (code "45") (name "Net-(V_R_12V_out-FB)") (class "Default")
      (node (ref "R13") (pin "1") (pintype "passive"))
      (node (ref "R14") (pin "2") (pintype "passive"))
      (node (ref "V_R_12V_out") (pin "8") (pinfunction "FB_8") (pintype "passive"))
    )
    (net (code "46") (name "Net-(V_R_12V_out-SS{slash}PG)") (class "Default")
      (node (ref "C20") (pin "1") (pintype "passive"))
      (node (ref "C21") (pin "1") (pintype "passive"))
      (node (ref "V_R_12V_out") (pin "7") (pinfunction "SS/PG_7") (pintype "passive"))
    )
    (net (code "47") (name "Net-(V_R_12V_out-SW)") (class "Default")
      (node (ref "C22") (pin "2") (pintype "passive"))
      (node (ref "L3") (pin "1") (pintype "passive"))
      (node (ref "V_R_12V_out") (pin "5") (pinfunction "SW_5") (pintype "power_in"))
    )
    (net (code "48") (name "V_Battery") (class "Default")
      (node (ref "C1") (pin "1") (pintype "passive"))
      (node (ref "C10") (pin "1") (pintype "passive"))
      (node (ref "C11") (pin "1") (pintype "passive"))
      (node (ref "C17") (pin "1") (pintype "passive"))
      (node (ref "C18") (pin "1") (pintype "passive"))
      (node (ref "C19") (pin "1") (pintype "passive"))
      (node (ref "C2") (pin "1") (pintype "passive"))
      (node (ref "C3") (pin "1") (pintype "passive"))
      (node (ref "C9") (pin "1") (pintype "passive"))
      (node (ref "D1") (pin "K") (pintype "passive"))
      (node (ref "D2") (pin "K") (pintype "passive"))
      (node (ref "D3") (pin "K") (pintype "passive"))
      (node (ref "Fuse") (pin "1") (pinfunction "1_1") (pintype "passive"))
      (node (ref "V_R_12V_out") (pin "3") (pinfunction "VIN_3") (pintype "power_in"))
      (node (ref "V_R_3.3V_out") (pin "3") (pinfunction "VIN_3") (pintype "power_in"))
      (node (ref "V_R_5V_out") (pin "3") (pinfunction "VIN_3") (pintype "power_in"))
    )
    (net (code "49") (name "unconnected-(Input_Lio-Pad01)") (class "Default")
      (node (ref "Input_Lio") (pin "01") (pinfunction "01_01") (pintype "passive+no_connect"))
    )
    (net (code "50") (name "unconnected-(Input_Lio-Pad02)") (class "Default")
      (node (ref "Input_Lio") (pin "02") (pinfunction "02_02") (pintype "passive+no_connect"))
    )
    (net (code "51") (name "unconnected-(Input_Lio-Pad03)") (class "Default")
      (node (ref "Input_Lio") (pin "03") (pinfunction "03_03") (pintype "passive+no_connect"))
    )
    (net (code "52") (name "unconnected-(Input_Lio-Pad04)") (class "Default")
      (node (ref "Input_Lio") (pin "04") (pinfunction "04_04") (pintype "passive+no_connect"))
    )
    (net (code "53") (name "unconnected-(Output_Lio-Pad01)") (class "Default")
      (node (ref "Output_Lio") (pin "01") (pinfunction "01_01") (pintype "passive+no_connect"))
    )
    (net (code "54") (name "unconnected-(V_R_3.3V_out-RT-Pad1)") (class "Default")
      (node (ref "V_R_3.3V_out") (pin "1") (pinfunction "RT_1") (pintype "passive+no_connect"))
    )
    (net (code "55") (name "unconnected-(V_R_5V_out-RT-Pad1)") (class "Default")
      (node (ref "V_R_5V_out") (pin "1") (pinfunction "RT_1") (pintype "passive+no_connect"))
    )
  )
)
